# top.net
KiCad netlist of a schematic drawn in EAGLE
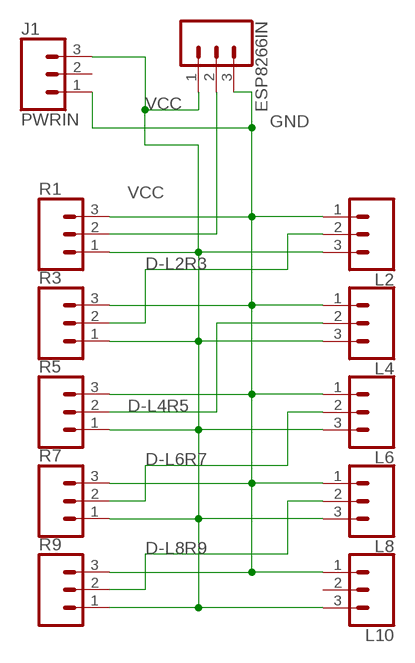
[diagram p0: schematic, sheet 1]

(export (version "E")
  (design (tool "Eeschema 10.0.6"))
  (components
    (comp (ref "ESP8266IN")
      (value "CONN_03")
      (footprint "eagle-import:1X03")
      (libsource (lib "eagle-import") (part "CONN_03"))
    )
    (comp (ref "J1")
      (value "PWRIN")
      (footprint "eagle-import:1X03")
      (libsource (lib "eagle-import") (part "CONN_03"))
    )
    (comp (ref "L2")
      (value "CONN_03")
      (footprint "eagle-import:1X03")
      (libsource (lib "eagle-import") (part "SparkFun-Connectors_513_CONN_03"))
    )
    (comp (ref "L4")
      (value "CONN_03")
      (footprint "eagle-import:1X03")
      (libsource (lib "eagle-import") (part "SparkFun-Connectors_513_CONN_03"))
    )
    (comp (ref "L6")
      (value "CONN_03")
      (footprint "eagle-import:1X03")
      (libsource (lib "eagle-import") (part "SparkFun-Connectors_513_CONN_03"))
    )
    (comp (ref "L8")
      (value "CONN_03")
      (footprint "eagle-import:1X03")
      (libsource (lib "eagle-import") (part "SparkFun-Connectors_513_CONN_03"))
    )
    (comp (ref "L10")
      (value "CONN_03")
      (footprint "eagle-import:1X03")
      (libsource (lib "eagle-import") (part "SparkFun-Connectors_513_CONN_03"))
    )
    (comp (ref "R1")
      (value "CONN_03")
      (footprint "eagle-import:1X03")
      (libsource (lib "eagle-import") (part "SparkFun-Connectors_513_CONN_03"))
    )
    (comp (ref "R3")
      (value "CONN_03")
      (footprint "eagle-import:1X03")
      (libsource (lib "eagle-import") (part "SparkFun-Connectors_513_CONN_03"))
    )
    (comp (ref "R5")
      (value "CONN_03")
      (footprint "eagle-import:1X03")
      (libsource (lib "eagle-import") (part "SparkFun-Connectors_513_CONN_03"))
    )
    (comp (ref "R7")
      (value "CONN_03")
      (footprint "eagle-import:1X03")
      (libsource (lib "eagle-import") (part "SparkFun-Connectors_513_CONN_03"))
    )
    (comp (ref "R9")
      (value "CONN_03")
      (footprint "eagle-import:1X03")
      (libsource (lib "eagle-import") (part "SparkFun-Connectors_513_CONN_03"))
    )
  )
  (nets
    (net (code "1") (name "/D-L2R3") (class "Default")
      (node (ref "L2") (pin "2") (pinfunction "2_2") (pintype "passive"))
      (node (ref "R3") (pin "2") (pinfunction "2_2") (pintype "passive"))
    )
    (net (code "2") (name "/D-L4R5") (class "Default")
      (node (ref "L4") (pin "2") (pinfunction "2_2") (pintype "passive"))
      (node (ref "R5") (pin "2") (pinfunction "2_2") (pintype "passive"))
    )
    (net (code "3") (name "/D-L6R7") (class "Default")
      (node (ref "L6") (pin "2") (pinfunction "2_2") (pintype "passive"))
      (node (ref "R7") (pin "2") (pinfunction "2_2") (pintype "passive"))
    )
    (net (code "4") (name "/D-L8R9") (class "Default")
      (node (ref "L8") (pin "2") (pinfunction "2_2") (pintype "passive"))
      (node (ref "R9") (pin "2") (pinfunction "2_2") (pintype "passive"))
    )
    (net (code "5") (name "/GND") (class "Default")
      (node (ref "ESP8266IN") (pin "3") (pinfunction "3_3") (pintype "passive"))
      (node (ref "J1") (pin "1") (pinfunction "1_1") (pintype "passive"))
      (node (ref "L10") (pin "1") (pinfunction "1_1") (pintype "passive"))
      (node (ref "L2") (pin "1") (pinfunction "1_1") (pintype "passive"))
      (node (ref "L4") (pin "1") (pinfunction "1_1") (pintype "passive"))
      (node (ref "L6") (pin "1") (pinfunction "1_1") (pintype "passive"))
      (node (ref "L8") (pin "1") (pinfunction "1_1") (pintype "passive"))
      (node (ref "R1") (pin "3") (pinfunction "3_3") (pintype "passive"))
      (node (ref "R3") (pin "3") (pinfunction "3_3") (pintype "passive"))
      (node (ref "R5") (pin "3") (pinfunction "3_3") (pintype "passive"))
      (node (ref "R7") (pin "3") (pinfunction "3_3") (pintype "passive"))
      (node (ref "R9") (pin "3") (pinfunction "3_3") (pintype "passive"))
    )
    (net (code "6") (name "/VCC") (class "Default")
      (node (ref "ESP8266IN") (pin "1") (pinfunction "1_1") (pintype "passive"))
      (node (ref "J1") (pin "3") (pinfunction "3_3") (pintype "passive"))
      (node (ref "L10") (pin "3") (pinfunction "3_3") (pintype "passive"))
      (node (ref "L2") (pin "3") (pinfunction "3_3") (pintype "passive"))
      (node (ref "L4") (pin "3") (pinfunction "3_3") (pintype "passive"))
      (node (ref "L6") (pin "3") (pinfunction "3_3") (pintype "passive"))
      (node (ref "L8") (pin "3") (pinfunction "3_3") (pintype "passive"))
      (node (ref "R1") (pin "1") (pinfunction "1_1") (pintype "passive"))
      (node (ref "R3") (pin "1") (pinfunction "1_1") (pintype "passive"))
      (node (ref "R5") (pin "1") (pinfunction "1_1") (pintype "passive"))
      (node (ref "R7") (pin "1") (pinfunction "1_1") (pintype "passive"))
      (node (ref "R9") (pin "1") (pinfunction "1_1") (pintype "passive"))
    )
    (net (code "7") (name "Net-(ESP8266IN-Pad2)") (class "Default")
      (node (ref "ESP8266IN") (pin "2") (pinfunction "2_2") (pintype "passive"))
      (node (ref "R1") (pin "2") (pinfunction "2_2") (pintype "passive"))
    )
    (net (code "8") (name "unconnected-(J1-Pad2)") (class "Default")
      (node (ref "J1") (pin "2") (pinfunction "2_2") (pintype "passive"))
    )
    (net (code "9") (name "unconnected-(L10-Pad2)") (class "Default")
      (node (ref "L10") (pin "2") (pinfunction "2_2") (pintype "passive"))
    )
  )
)
